# Alat_Cuci_Beras.net
KiCad netlist of a schematic drawn in EAGLE
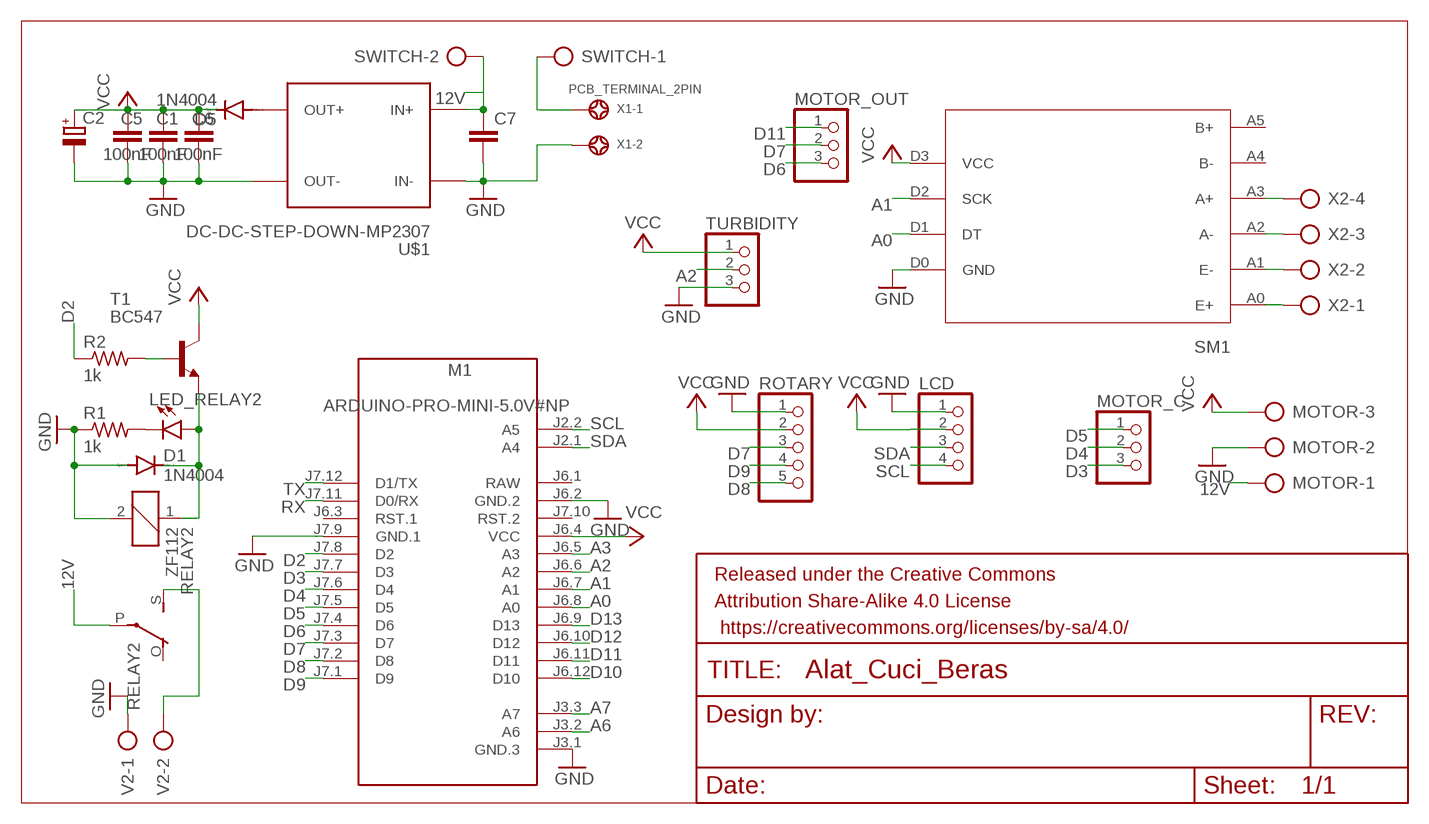
[diagram p0: schematic, sheet 1]

(export (version "E")
  (design (tool "Eeschema 10.0.6"))
  (components
    (comp (ref "C1")
      (value "100nF")
      (footprint "eagle-import:C0805K")
      (libsource (lib "eagle-import") (part "C-EUC0805K"))
    )
    (comp (ref "C2")
      (value "CPOL-EUE2.5-6")
      (footprint "eagle-import:E2,5-6")
      (libsource (lib "eagle-import") (part "CPOL-EUE2.5-6"))
    )
    (comp (ref "C5")
      (value "100nF")
      (footprint "eagle-import:C0805K")
      (libsource (lib "eagle-import") (part "C-EUC0805K"))
    )
    (comp (ref "C6")
      (value "100nF")
      (footprint "eagle-import:C0805K")
      (libsource (lib "eagle-import") (part "C-EUC0805K"))
    )
    (comp (ref "C7")
      (value "C-EU050-030X075")
      (footprint "eagle-import:C050-030X075")
      (libsource (lib "eagle-import") (part "C-EU050-030X075"))
    )
    (comp (ref "D1")
      (value "1N4004")
      (footprint "eagle-import:DO41-10")
      (libsource (lib "eagle-import") (part "1N4004"))
    )
    (comp (ref "D5")
      (value "1N4004")
      (footprint "eagle-import:DO41-10")
      (libsource (lib "eagle-import") (part "1N4004"))
    )
    (comp (ref "FRAME1")
      (value "FRAME-LETTER")
      (footprint "eagle-import:CREATIVE_COMMONS")
      (libsource (lib "eagle-import") (part "FRAME-LETTER"))
    )
    (comp (ref "LCD")
      (value "PINHD-1X4")
      (footprint "eagle-import:1X04")
      (libsource (lib "eagle-import") (part "PINHD-1X4"))
    )
    (comp (ref "LED_RELAY2")
      (value "LED3MM")
      (footprint "eagle-import:LED_3MM")
      (libsource (lib "eagle-import") (part "LED3MM"))
    )
    (comp (ref "M1")
      (value "ARDUINO-PRO-MINI-5.0V#NP")
      (footprint "eagle-import:ARDUINO-PRO-MINI#NP")
      (libsource (lib "eagle-import") (part "ARDUINO-PRO-MINI-#NP5.0V"))
    )
    (comp (ref "MOTOR")
      (value "AK500/3")
      (footprint "eagle-import:AK500_3")
      (libsource (lib "eagle-import") (part "AK500/3"))
    )
    (comp (ref "MOTOR_C")
      (value "PINHD-1X3")
      (footprint "eagle-import:1X03")
      (libsource (lib "eagle-import") (part "PINHD-1X3"))
    )
    (comp (ref "MOTOR_OUT")
      (value "PINHD-1X3")
      (footprint "eagle-import:1X03")
      (libsource (lib "eagle-import") (part "PINHD-1X3"))
    )
    (comp (ref "R1")
      (value "1k")
      (footprint "eagle-import:R0805")
      (libsource (lib "eagle-import") (part "R-US_R0805"))
    )
    (comp (ref "R2")
      (value "1k")
      (footprint "eagle-import:0207_10")
      (libsource (lib "eagle-import") (part "R-US_0207/10"))
    )
    (comp (ref "RELAY2")
      (value "ZF112")
      (footprint "eagle-import:ZF112")
      (libsource (lib "eagle-import") (part "ZF112"))
    )
    (comp (ref "ROTARY")
      (value "PINHD-1X5")
      (footprint "eagle-import:1X05")
      (libsource (lib "eagle-import") (part "PINHD-1X5"))
    )
    (comp (ref "SM1")
      (value "HX711")
      (footprint "eagle-import:HX711")
      (libsource (lib "eagle-import") (part "HX711"))
    )
    (comp (ref "SWITCH")
      (value "AK500/2")
      (footprint "eagle-import:AK500_2")
      (libsource (lib "eagle-import") (part "AK500/2"))
    )
    (comp (ref "T1")
      (value "BC547")
      (footprint "eagle-import:TO92")
      (libsource (lib "eagle-import") (part "BC547"))
    )
    (comp (ref "TURBIDITY")
      (value "PINHD-1X3")
      (footprint "eagle-import:1X03")
      (libsource (lib "eagle-import") (part "PINHD-1X3"))
    )
    (comp (ref "U$1")
      (value "DC-DC-STEP-DOWN-MP2307")
      (footprint "eagle-import:DC-DC-STEP-DOWN-MP2307")
      (libsource (lib "eagle-import") (part "DC-DC-STEP-DOWN-MP2307"))
    )
    (comp (ref "V2")
      (value "AK500/2")
      (footprint "eagle-import:AK500_2")
      (libsource (lib "eagle-import") (part "AK500/2"))
    )
    (comp (ref "X1")
      (value "PCB_TERMINAL_2PIN")
      (footprint "eagle-import:PCB_TERMINAL_2PIN")
      (libsource (lib "eagle-import") (part "PCB_TERMINAL_2PIN"))
    )
    (comp (ref "X2")
      (value "AK500/4")
      (footprint "eagle-import:AK500_4")
      (libsource (lib "eagle-import") (part "AK500/4"))
    )
  )
  (nets
    (net (code "1") (name "/12V") (class "Default")
      (node (ref "C7") (pin "1") (pinfunction "1_1") (pintype "passive"))
      (node (ref "MOTOR") (pin "1") (pinfunction "KL_1") (pintype "passive"))
      (node (ref "RELAY2") (pin "P") (pinfunction "P_P") (pintype "passive"))
      (node (ref "SWITCH") (pin "2") (pinfunction "KL_2") (pintype "passive"))
      (node (ref "U$1") (pin "IN+") (pinfunction "IN+_IN+") (pintype "bidirectional"))
    )
    (net (code "2") (name "/A0") (class "Default")
      (node (ref "M1") (pin "J6.8") (pinfunction "A0_J6.8") (pintype "bidirectional"))
      (node (ref "SM1") (pin "D1") (pinfunction "DT_D1") (pintype "bidirectional"))
    )
    (net (code "3") (name "/A1") (class "Default")
      (node (ref "M1") (pin "J6.7") (pinfunction "A1_J6.7") (pintype "bidirectional"))
      (node (ref "SM1") (pin "D2") (pinfunction "SCK_D2") (pintype "bidirectional"))
    )
    (net (code "4") (name "/A2") (class "Default")
      (node (ref "M1") (pin "J6.6") (pinfunction "A2_J6.6") (pintype "bidirectional"))
      (node (ref "TURBIDITY") (pin "2") (pinfunction "2_2") (pintype "passive"))
    )
    (net (code "5") (name "/A3") (class "Default")
      (node (ref "M1") (pin "J6.5") (pinfunction "A3_J6.5") (pintype "bidirectional"))
    )
    (net (code "6") (name "/A6") (class "Default")
      (node (ref "M1") (pin "J3.2") (pinfunction "A6_J3.2") (pintype "bidirectional"))
    )
    (net (code "7") (name "/A7") (class "Default")
      (node (ref "M1") (pin "J3.3") (pinfunction "A7_J3.3") (pintype "bidirectional"))
    )
    (net (code "8") (name "/D2") (class "Default")
      (node (ref "M1") (pin "J7.8") (pinfunction "D2_J7.8") (pintype "bidirectional"))
      (node (ref "R2") (pin "1") (pinfunction "1_1") (pintype "passive"))
    )
    (net (code "9") (name "/D3") (class "Default")
      (node (ref "M1") (pin "J7.7") (pinfunction "D3_J7.7") (pintype "bidirectional"))
      (node (ref "MOTOR_C") (pin "3") (pinfunction "3_3") (pintype "passive"))
    )
    (net (code "10") (name "/D4") (class "Default")
      (node (ref "M1") (pin "J7.6") (pinfunction "D4_J7.6") (pintype "bidirectional"))
      (node (ref "MOTOR_C") (pin "2") (pinfunction "2_2") (pintype "passive"))
    )
    (net (code "11") (name "/D5") (class "Default")
      (node (ref "M1") (pin "J7.5") (pinfunction "D5_J7.5") (pintype "bidirectional"))
      (node (ref "MOTOR_C") (pin "1") (pinfunction "1_1") (pintype "passive"))
    )
    (net (code "12") (name "/D6") (class "Default")
      (node (ref "M1") (pin "J7.4") (pinfunction "D6_J7.4") (pintype "bidirectional"))
      (node (ref "MOTOR_OUT") (pin "3") (pinfunction "3_3") (pintype "passive"))
    )
    (net (code "13") (name "/D7") (class "Default")
      (node (ref "M1") (pin "J7.3") (pinfunction "D7_J7.3") (pintype "bidirectional"))
      (node (ref "MOTOR_OUT") (pin "2") (pinfunction "2_2") (pintype "passive"))
      (node (ref "ROTARY") (pin "3") (pinfunction "3_3") (pintype "passive"))
    )
    (net (code "14") (name "/D8") (class "Default")
      (node (ref "M1") (pin "J7.2") (pinfunction "D8_J7.2") (pintype "bidirectional"))
      (node (ref "ROTARY") (pin "5") (pinfunction "5_5") (pintype "passive"))
    )
    (net (code "15") (name "/D9") (class "Default")
      (node (ref "M1") (pin "J7.1") (pinfunction "D9_J7.1") (pintype "bidirectional"))
      (node (ref "ROTARY") (pin "4") (pinfunction "4_4") (pintype "passive"))
    )
    (net (code "16") (name "/D10") (class "Default")
      (node (ref "M1") (pin "J6.12") (pinfunction "D10_J6.12") (pintype "bidirectional"))
    )
    (net (code "17") (name "/D11") (class "Default")
      (node (ref "M1") (pin "J6.11") (pinfunction "D11_J6.11") (pintype "bidirectional"))
      (node (ref "MOTOR_OUT") (pin "1") (pinfunction "1_1") (pintype "passive"))
    )
    (net (code "18") (name "/D12") (class "Default")
      (node (ref "M1") (pin "J6.10") (pinfunction "D12_J6.10") (pintype "bidirectional"))
    )
    (net (code "19") (name "/D13") (class "Default")
      (node (ref "M1") (pin "J6.9") (pinfunction "D13_J6.9") (pintype "bidirectional"))
    )
    (net (code "20") (name "/RAW") (class "Default")
      (node (ref "M1") (pin "J6.1") (pinfunction "RAW_J6.1") (pintype "power_in"))
    )
    (net (code "21") (name "/RX") (class "Default")
      (node (ref "M1") (pin "J7.11") (pinfunction "D0/RX_J7.11") (pintype "bidirectional"))
    )
    (net (code "22") (name "/SCL") (class "Default")
      (node (ref "LCD") (pin "4") (pinfunction "4_4") (pintype "passive"))
      (node (ref "M1") (pin "J2.2") (pinfunction "A5_J2.2") (pintype "bidirectional"))
    )
    (net (code "23") (name "/SDA") (class "Default")
      (node (ref "LCD") (pin "3") (pinfunction "3_3") (pintype "passive"))
      (node (ref "M1") (pin "J2.1") (pinfunction "A4_J2.1") (pintype "bidirectional"))
    )
    (net (code "24") (name "/TX") (class "Default")
      (node (ref "M1") (pin "J7.12") (pinfunction "D1/TX_J7.12") (pintype "bidirectional"))
    )
    (net (code "25") (name "GND") (class "Default")
      (node (ref "C1") (pin "2") (pinfunction "2_2") (pintype "passive"))
      (node (ref "C2") (pin "-") (pinfunction "-_-") (pintype "passive"))
      (node (ref "C5") (pin "2") (pinfunction "2_2") (pintype "passive"))
      (node (ref "C6") (pin "2") (pinfunction "2_2") (pintype "passive"))
      (node (ref "C7") (pin "2") (pinfunction "2_2") (pintype "passive"))
      (node (ref "D1") (pin "A") (pinfunction "A_A") (pintype "passive"))
      (node (ref "LCD") (pin "1") (pinfunction "1_1") (pintype "passive"))
      (node (ref "M1") (pin "J3.1") (pinfunction "GND.3_J3.1") (pintype "bidirectional"))
      (node (ref "M1") (pin "J6.2") (pinfunction "GND.2_J6.2") (pintype "power_in"))
      (node (ref "M1") (pin "J7.9") (pinfunction "GND.1_J7.9") (pintype "power_in"))
      (node (ref "MOTOR") (pin "2") (pinfunction "KL_2") (pintype "passive"))
      (node (ref "R1") (pin "1") (pinfunction "1_1") (pintype "passive"))
      (node (ref "RELAY2") (pin "2") (pinfunction "2_2") (pintype "passive"))
      (node (ref "ROTARY") (pin "1") (pinfunction "1_1") (pintype "passive"))
      (node (ref "SM1") (pin "D0") (pinfunction "GND_D0") (pintype "bidirectional"))
      (node (ref "TURBIDITY") (pin "3") (pinfunction "3_3") (pintype "passive"))
      (node (ref "U$1") (pin "IN-") (pinfunction "IN-_IN-") (pintype "bidirectional"))
      (node (ref "U$1") (pin "OUT-") (pinfunction "OUT-_OUT-") (pintype "bidirectional"))
      (node (ref "V2") (pin "1") (pinfunction "KL_1") (pintype "passive"))
      (node (ref "X1") (pin "2") (pinfunction "1_2") (pintype "passive"))
    )
    (net (code "26") (name "Net-(D5-PadA)") (class "Default")
      (node (ref "D5") (pin "A") (pinfunction "A_A") (pintype "passive"))
      (node (ref "U$1") (pin "OUT+") (pinfunction "OUT+_OUT+") (pintype "bidirectional"))
    )
    (net (code "27") (name "Net-(LED_RELAY2-C)") (class "Default")
      (node (ref "LED_RELAY2") (pin "K") (pinfunction "C_K") (pintype "passive"))
      (node (ref "R1") (pin "2") (pinfunction "2_2") (pintype "passive"))
    )
    (net (code "28") (name "Net-(SM1-A+)") (class "Default")
      (node (ref "SM1") (pin "A3") (pinfunction "A+_A3") (pintype "bidirectional"))
      (node (ref "X2") (pin "4") (pinfunction "KL_4") (pintype "passive"))
    )
    (net (code "29") (name "Net-(SM1-A-)") (class "Default")
      (node (ref "SM1") (pin "A2") (pinfunction "A-_A2") (pintype "bidirectional"))
      (node (ref "X2") (pin "3") (pinfunction "KL_3") (pintype "passive"))
    )
    (net (code "30") (name "Net-(SM1-E+)") (class "Default")
      (node (ref "SM1") (pin "A0") (pinfunction "E+_A0") (pintype "bidirectional"))
      (node (ref "X2") (pin "1") (pinfunction "KL_1") (pintype "passive"))
    )
    (net (code "31") (name "Net-(SM1-E-)") (class "Default")
      (node (ref "SM1") (pin "A1") (pinfunction "E-_A1") (pintype "bidirectional"))
      (node (ref "X2") (pin "2") (pinfunction "KL_2") (pintype "passive"))
    )
    (net (code "32") (name "Net-(SWITCHA-KL)") (class "Default")
      (node (ref "SWITCH") (pin "1") (pinfunction "KL_1") (pintype "passive"))
      (node (ref "X1") (pin "1") (pinfunction "1_1") (pintype "passive"))
    )
    (net (code "33") (name "Net-(T1-B)") (class "Default")
      (node (ref "R2") (pin "2") (pinfunction "2_2") (pintype "passive"))
      (node (ref "T1") (pin "2") (pinfunction "B_2") (pintype "passive"))
    )
    (net (code "34") (name "Net-(T1-E)") (class "Default")
      (node (ref "D1") (pin "C") (pinfunction "C_C") (pintype "passive"))
      (node (ref "LED_RELAY2") (pin "A") (pinfunction "A_A") (pintype "passive"))
      (node (ref "RELAY2") (pin "1") (pinfunction "1_1") (pintype "passive"))
      (node (ref "T1") (pin "1") (pinfunction "E_1") (pintype "passive"))
    )
    (net (code "35") (name "Net-(V2B-KL)") (class "Default")
      (node (ref "RELAY2") (pin "S") (pinfunction "S_S") (pintype "passive"))
      (node (ref "V2") (pin "2") (pinfunction "KL_2") (pintype "passive"))
    )
    (net (code "36") (name "VCC") (class "Default")
      (node (ref "C1") (pin "1") (pinfunction "1_1") (pintype "passive"))
      (node (ref "C2") (pin "+") (pinfunction "+_+") (pintype "passive"))
      (node (ref "C5") (pin "1") (pinfunction "1_1") (pintype "passive"))
      (node (ref "C6") (pin "1") (pinfunction "1_1") (pintype "passive"))
      (node (ref "D5") (pin "C") (pinfunction "C_C") (pintype "passive"))
      (node (ref "LCD") (pin "2") (pinfunction "2_2") (pintype "passive"))
      (node (ref "M1") (pin "J6.4") (pinfunction "VCC_J6.4") (pintype "power_in"))
      (node (ref "MOTOR") (pin "3") (pinfunction "KL_3") (pintype "passive"))
      (node (ref "ROTARY") (pin "2") (pinfunction "2_2") (pintype "passive"))
      (node (ref "SM1") (pin "D3") (pinfunction "VCC_D3") (pintype "bidirectional"))
      (node (ref "T1") (pin "3") (pinfunction "C_3") (pintype "passive"))
      (node (ref "TURBIDITY") (pin "1") (pinfunction "1_1") (pintype "passive"))
    )
    (net (code "37") (name "unconnected-(M1-RST.1-PadJ6.3)") (class "Default")
      (node (ref "M1") (pin "J6.3") (pinfunction "RST.1_J6.3") (pintype "bidirectional"))
    )
    (net (code "38") (name "unconnected-(M1-RST.2-PadJ7.10)") (class "Default")
      (node (ref "M1") (pin "J7.10") (pinfunction "RST.2_J7.10") (pintype "bidirectional"))
    )
    (net (code "39") (name "unconnected-(RELAY2-PadO)") (class "Default")
      (node (ref "RELAY2") (pin "O") (pinfunction "O_O") (pintype "passive"))
    )
    (net (code "40") (name "unconnected-(SM1-B+-PadA5)") (class "Default")
      (node (ref "SM1") (pin "A5") (pinfunction "B+_A5") (pintype "bidirectional"))
    )
    (net (code "41") (name "unconnected-(SM1-B--PadA4)") (class "Default")
      (node (ref "SM1") (pin "A4") (pinfunction "B-_A4") (pintype "bidirectional"))
    )
  )
)
